# Strum.net
KiCad netlist of a schematic drawn in Altium Designer
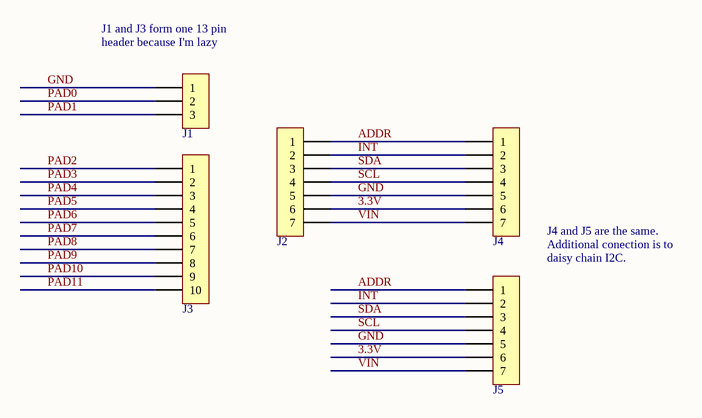
[diagram p0: Strum.SchDoc]

(export (version "E")
  (design (tool "Eeschema 10.0.6"))
  (components
    (comp (ref "J1")
      (value "3-644456-3")
      (footprint "TE_3-644456-3")
      (description "CONN HEADER VERT 3POS .100 TIN")
      (fields (field (name "MANUFACTURER") "TE Connectivity"))
      (libsource (lib "Connectors") (part "HEADER_1x3"))
    )
    (comp (ref "J2")
      (value "3-644456-7")
      (footprint "TE_3-644456-7")
      (description "CONN HEADER VERT 7POS .100 TIN")
      (fields (field (name "MANUFACTURER") "TE Connectivity"))
      (libsource (lib "Connectors") (part "HEADER_1x7"))
    )
    (comp (ref "J3")
      (value "4-644456-0")
      (footprint "TE_4-644456-0")
      (description "CONN HEADER VERT 10POS .100 TIN")
      (fields (field (name "MANUFACTURER") "TE Connectivity AMP Connectors"))
      (libsource (lib "Connectors") (part "HEADER_1x10"))
    )
    (comp (ref "J4")
      (value "3-644456-7")
      (footprint "TE_3-644456-7")
      (description "CONN HEADER VERT 7POS .100 TIN")
      (fields (field (name "MANUFACTURER") "TE Connectivity"))
      (libsource (lib "") (part "HEADER_1x7_1"))
    )
    (comp (ref "J5")
      (value "3-644456-7")
      (footprint "TE_3-644456-7")
      (description "CONN HEADER VERT 7POS .100 TIN")
      (fields (field (name "MANUFACTURER") "TE Connectivity"))
      (libsource (lib "") (part "HEADER_1x7_1"))
    )
  )
  (nets
    (net (code "1") (name "/3.3V") (class "Default")
      (node (ref "J2") (pin "6") (pinfunction "6_6") (pintype "passive"))
      (node (ref "J4") (pin "6") (pinfunction "6_6") (pintype "passive"))
      (node (ref "J5") (pin "6") (pinfunction "6_6") (pintype "passive"))
    )
    (net (code "2") (name "/ADDR") (class "Default")
      (node (ref "J2") (pin "1") (pinfunction "1_1") (pintype "passive"))
      (node (ref "J4") (pin "1") (pinfunction "1_1") (pintype "passive"))
      (node (ref "J5") (pin "1") (pinfunction "1_1") (pintype "passive"))
    )
    (net (code "3") (name "/GND") (class "Default")
      (node (ref "J1") (pin "1") (pinfunction "1_1") (pintype "passive"))
      (node (ref "J2") (pin "5") (pinfunction "5_5") (pintype "passive"))
      (node (ref "J4") (pin "5") (pinfunction "5_5") (pintype "passive"))
      (node (ref "J5") (pin "5") (pinfunction "5_5") (pintype "passive"))
    )
    (net (code "4") (name "/INT") (class "Default")
      (node (ref "J2") (pin "2") (pinfunction "2_2") (pintype "passive"))
      (node (ref "J4") (pin "2") (pinfunction "2_2") (pintype "passive"))
      (node (ref "J5") (pin "2") (pinfunction "2_2") (pintype "passive"))
    )
    (net (code "5") (name "/PAD0") (class "Default")
      (node (ref "J1") (pin "2") (pinfunction "2_2") (pintype "passive"))
    )
    (net (code "6") (name "/PAD1") (class "Default")
      (node (ref "J1") (pin "3") (pinfunction "3_3") (pintype "passive"))
    )
    (net (code "7") (name "/PAD2") (class "Default")
      (node (ref "J3") (pin "1") (pinfunction "1_1") (pintype "passive"))
    )
    (net (code "8") (name "/PAD3") (class "Default")
      (node (ref "J3") (pin "2") (pinfunction "2_2") (pintype "passive"))
    )
    (net (code "9") (name "/PAD4") (class "Default")
      (node (ref "J3") (pin "3") (pinfunction "3_3") (pintype "passive"))
    )
    (net (code "10") (name "/PAD5") (class "Default")
      (node (ref "J3") (pin "4") (pinfunction "4_4") (pintype "passive"))
    )
    (net (code "11") (name "/PAD6") (class "Default")
      (node (ref "J3") (pin "5") (pinfunction "5_5") (pintype "passive"))
    )
    (net (code "12") (name "/PAD7") (class "Default")
      (node (ref "J3") (pin "6") (pinfunction "6_6") (pintype "passive"))
    )
    (net (code "13") (name "/PAD8") (class "Default")
      (node (ref "J3") (pin "7") (pinfunction "7_7") (pintype "passive"))
    )
    (net (code "14") (name "/PAD9") (class "Default")
      (node (ref "J3") (pin "8") (pinfunction "8_8") (pintype "passive"))
    )
    (net (code "15") (name "/PAD10") (class "Default")
      (node (ref "J3") (pin "9") (pinfunction "9_9") (pintype "passive"))
    )
    (net (code "16") (name "/PAD11") (class "Default")
      (node (ref "J3") (pin "10") (pinfunction "10_10") (pintype "passive"))
    )
    (net (code "17") (name "/SCL") (class "Default")
      (node (ref "J2") (pin "4") (pinfunction "4_4") (pintype "passive"))
      (node (ref "J4") (pin "4") (pinfunction "4_4") (pintype "passive"))
      (node (ref "J5") (pin "4") (pinfunction "4_4") (pintype "passive"))
    )
    (net (code "18") (name "/SDA") (class "Default")
      (node (ref "J2") (pin "3") (pinfunction "3_3") (pintype "passive"))
      (node (ref "J4") (pin "3") (pinfunction "3_3") (pintype "passive"))
      (node (ref "J5") (pin "3") (pinfunction "3_3") (pintype "passive"))
    )
    (net (code "19") (name "/VIN") (class "Default")
      (node (ref "J2") (pin "7") (pinfunction "7_7") (pintype "passive"))
      (node (ref "J4") (pin "7") (pinfunction "7_7") (pintype "passive"))
      (node (ref "J5") (pin "7") (pinfunction "7_7") (pintype "passive"))
    )
  )
)
